# LM2595s-5_0.net
KiCad netlist of a schematic drawn in Altium Designer
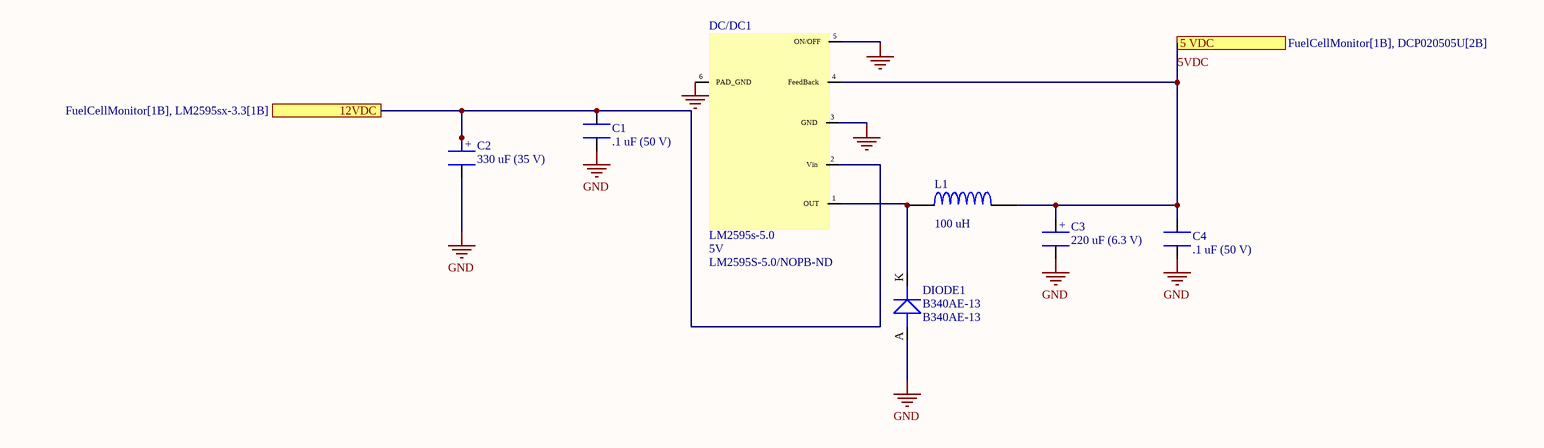
[diagram p0: LM2595s-5.0.SchDoc]

(export (version "E")
  (design (tool "Eeschema 10.0.6"))
  (components
    (comp (ref "C1")
      (value ".1 uF (50 V)")
      (footprint ".1uF capacitor")
      (libsource (lib "FuelCellMonitor") (part ".1 uF cap"))
    )
    (comp (ref "C2")
      (value "330 uF (35 V)")
      (footprint "330uf cap")
      (libsource (lib "FuelCellMonitor") (part "330 uF cap"))
    )
    (comp (ref "C3")
      (value "220 uF (6.3 V)")
      (footprint "220 uf cap")
      (libsource (lib "FuelCellMonitor") (part "220 uF capacitor"))
    )
    (comp (ref "C4")
      (value ".1 uF (50 V)")
      (footprint ".1uF capacitor")
      (libsource (lib "FuelCellMonitor") (part ".1 uF cap"))
    )
    (comp (ref "DC/DC1")
      (value "LM2595s-5.0")
      (footprint "LM2595s-5.0")
      (description "SIMPLE SWITCHE Power Converter 150 KHz 1A Step-Down Voltage egulator 5-DDPAK/TO-263")
      (fields
        (field (name "MANUFACTURER") "Texas Instruments")
        (field (name "MANUFACTURER PART NUMBER") "LM2595S-5.0/NOPB")
        (field (name "OUTPUT VOLTAGE") "5V")
        (field (name "SUPPLIER PART NUMBER 1") "LM2595S-5.0/NOPB-ND")
      )
      (libsource (lib "FuelCellMonitor") (part "LM2595S-5.0/NOPB"))
    )
    (comp (ref "DIODE1")
      (value "B340AE-13")
      (footprint "B340AE-13")
      (description "Schottky Diode, DO-201, 40V, 3.00A")
      (fields
        (field (name "MANUFACTURER") "STMicroelectronics")
        (field (name "MANUFACTURER PART NUMBER") "B340AE-13")
      )
      (libsource (lib "FuelCellMonitor") (part "B340AE-13"))
    )
    (comp (ref "L1")
      (value "100 uH")
      (footprint "100uH inductor")
      (libsource (lib "FuelCellMonitor") (part "100 uH inductor"))
    )
  )
  (nets
    (net (code "1") (name "/5VDC") (class "Default")
      (node (ref "C3") (pin "1") (pinfunction "1_1") (pintype "power_in"))
      (node (ref "C4") (pin "2") (pinfunction "2_2") (pintype "power_in"))
      (node (ref "DC/DC1") (pin "4") (pinfunction "FeedBack_4") (pintype "power_in"))
      (node (ref "L1") (pin "2") (pinfunction "2_2") (pintype "passive"))
    )
    (net (code "2") (name "/12VDC") (class "Default")
      (node (ref "C1") (pin "2") (pinfunction "2_2") (pintype "power_in"))
      (node (ref "C2") (pin "1") (pinfunction "1_1") (pintype "power_in"))
      (node (ref "DC/DC1") (pin "2") (pinfunction "Vin_2") (pintype "power_in"))
    )
    (net (code "3") (name "GND") (class "Default")
      (node (ref "C1") (pin "1") (pinfunction "1_1") (pintype "power_in"))
      (node (ref "C2") (pin "2") (pinfunction "2_2") (pintype "power_in"))
      (node (ref "C3") (pin "2") (pinfunction "2_2") (pintype "power_in"))
      (node (ref "C4") (pin "1") (pinfunction "1_1") (pintype "power_in"))
      (node (ref "DC/DC1") (pin "3") (pinfunction "GND_3") (pintype "power_in"))
      (node (ref "DC/DC1") (pin "5") (pinfunction "ON/OFF_5") (pintype "power_in"))
      (node (ref "DC/DC1") (pin "6") (pinfunction "PAD_GND_6") (pintype "power_in"))
      (node (ref "DIODE1") (pin "A") (pinfunction "A_A") (pintype "power_in"))
    )
    (net (code "4") (name "Net-(DC/DC1-OUT)") (class "Default")
      (node (ref "DC/DC1") (pin "1") (pinfunction "OUT_1") (pintype "power_in"))
      (node (ref "DIODE1") (pin "K") (pinfunction "K_K") (pintype "power_in"))
      (node (ref "L1") (pin "1") (pinfunction "1_1") (pintype "passive"))
    )
  )
)
